# Strain_Gauges_Amplifier_TH.net
KiCad netlist of a schematic drawn in EAGLE
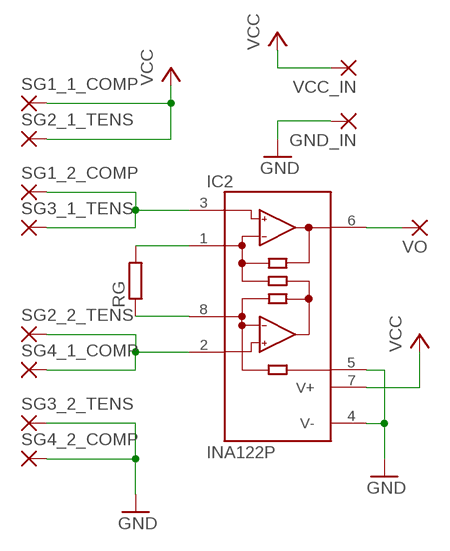
[diagram p0: schematic, sheet 1]

(export (version "E")
  (design (tool "Eeschema 10.0.6"))
  (components
    (comp (ref "GND_IN")
      (value "SMD2")
      (footprint "eagle-import:SMD1,27-2,54")
      (libsource (lib "eagle-import") (part "SMD2"))
    )
    (comp (ref "IC2")
      (value "INA122P")
      (footprint "eagle-import:DIL08")
      (fields (field (name "MF") "TEXAS INSTRUMENTS"))
      (libsource (lib "eagle-import") (part "INA122P"))
    )
    (comp (ref "RG")
      (value "R-EU_0204/7")
      (footprint "eagle-import:0204_7")
      (libsource (lib "eagle-import") (part "R-EU_0204/7"))
    )
    (comp (ref "SG1_1_COMP")
      (value "SMD2")
      (footprint "eagle-import:SMD1,27-2,54")
      (libsource (lib "eagle-import") (part "SMD2"))
    )
    (comp (ref "SG1_2_COMP")
      (value "SMD2")
      (footprint "eagle-import:SMD1,27-2,54")
      (libsource (lib "eagle-import") (part "SMD2"))
    )
    (comp (ref "SG2_1_TENS")
      (value "SMD2")
      (footprint "eagle-import:SMD1,27-2,54")
      (libsource (lib "eagle-import") (part "SMD2"))
    )
    (comp (ref "SG2_2_TENS")
      (value "SMD2")
      (footprint "eagle-import:SMD1,27-2,54")
      (libsource (lib "eagle-import") (part "SMD2"))
    )
    (comp (ref "SG3_1_TENS")
      (value "SMD2")
      (footprint "eagle-import:SMD1,27-2,54")
      (libsource (lib "eagle-import") (part "SMD2"))
    )
    (comp (ref "SG3_2_TENS")
      (value "SMD2")
      (footprint "eagle-import:SMD1,27-2,54")
      (libsource (lib "eagle-import") (part "SMD2"))
    )
    (comp (ref "SG4_1_COMP")
      (value "SMD2")
      (footprint "eagle-import:SMD1,27-2,54")
      (libsource (lib "eagle-import") (part "SMD2"))
    )
    (comp (ref "SG4_2_COMP")
      (value "SMD2")
      (footprint "eagle-import:SMD1,27-2,54")
      (libsource (lib "eagle-import") (part "SMD2"))
    )
    (comp (ref "VCC_IN")
      (value "SMD2")
      (footprint "eagle-import:SMD1,27-2,54")
      (libsource (lib "eagle-import") (part "SMD2"))
    )
    (comp (ref "VO")
      (value "SMD2")
      (footprint "eagle-import:SMD1,27-2,54")
      (libsource (lib "eagle-import") (part "SMD2"))
    )
  )
  (nets
    (net (code "1") (name "GND") (class "Default")
      (node (ref "GND_IN") (pin "1") (pinfunction "P_1") (pintype "passive"))
      (node (ref "IC2") (pin "4") (pinfunction "V-_4") (pintype "power_in"))
      (node (ref "IC2") (pin "5") (pinfunction "REF_5") (pintype "passive"))
      (node (ref "SG3_2_TENS") (pin "1") (pinfunction "P_1") (pintype "passive"))
      (node (ref "SG4_2_COMP") (pin "1") (pinfunction "P_1") (pintype "passive"))
    )
    (net (code "2") (name "Net-(IC2-+IN)") (class "Default")
      (node (ref "IC2") (pin "3") (pinfunction "+IN_3") (pintype "input"))
      (node (ref "SG1_2_COMP") (pin "1") (pinfunction "P_1") (pintype "passive"))
      (node (ref "SG3_1_TENS") (pin "1") (pinfunction "P_1") (pintype "passive"))
    )
    (net (code "3") (name "Net-(IC2--IN)") (class "Default")
      (node (ref "IC2") (pin "2") (pinfunction "-IN_2") (pintype "input"))
      (node (ref "SG2_2_TENS") (pin "1") (pinfunction "P_1") (pintype "passive"))
      (node (ref "SG4_1_COMP") (pin "1") (pinfunction "P_1") (pintype "passive"))
    )
    (net (code "4") (name "Net-(IC2-OUT)") (class "Default")
      (node (ref "IC2") (pin "6") (pinfunction "OUT_6") (pintype "output"))
      (node (ref "VO") (pin "1") (pinfunction "P_1") (pintype "passive"))
    )
    (net (code "5") (name "Net-(IC2-RG-Pad1)") (class "Default")
      (node (ref "IC2") (pin "1") (pinfunction "RG_1") (pintype "passive"))
      (node (ref "RG") (pin "2") (pinfunction "2_2") (pintype "passive"))
    )
    (net (code "6") (name "Net-(IC2-RG-Pad8)") (class "Default")
      (node (ref "IC2") (pin "8") (pinfunction "RG_8") (pintype "passive"))
      (node (ref "RG") (pin "1") (pinfunction "1_1") (pintype "passive"))
    )
    (net (code "7") (name "VCC") (class "Default")
      (node (ref "IC2") (pin "7") (pinfunction "V+_7") (pintype "power_in"))
      (node (ref "SG1_1_COMP") (pin "1") (pinfunction "P_1") (pintype "passive"))
      (node (ref "SG2_1_TENS") (pin "1") (pinfunction "P_1") (pintype "passive"))
      (node (ref "VCC_IN") (pin "1") (pinfunction "P_1") (pintype "passive"))
    )
  )
)
